# DETECTOR01.net
KiCad netlist of a schematic drawn in EAGLE
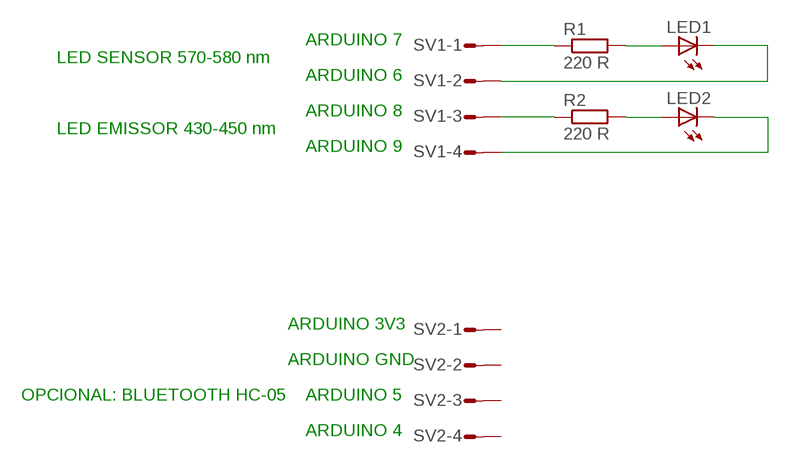
[diagram p0: schematic, sheet 1]

(export (version "E")
  (design (tool "Eeschema 10.0.6"))
  (components
    (comp (ref "LED1")
      (value "LED5MM")
      (footprint "eagle-import:LED5MM")
      (libsource (lib "eagle-import") (part "LED5MM"))
    )
    (comp (ref "LED2")
      (value "LED5MM")
      (footprint "eagle-import:LED5MM")
      (libsource (lib "eagle-import") (part "LED5MM"))
    )
    (comp (ref "R1")
      (value "220 R")
      (footprint "eagle-import:0204_7")
      (libsource (lib "eagle-import") (part "R-EU_0204/7"))
    )
    (comp (ref "R2")
      (value "220 R")
      (footprint "eagle-import:0204_7")
      (libsource (lib "eagle-import") (part "R-EU_0204/7"))
    )
    (comp (ref "SV1")
      (value "L04P")
      (footprint "eagle-import:L04P")
      (libsource (lib "eagle-import") (part "L04P"))
    )
    (comp (ref "SV2")
      (value "L04P")
      (footprint "eagle-import:L04P")
      (libsource (lib "eagle-import") (part "L04P"))
    )
  )
  (nets
    (net (code "1") (name "Net-(LED1-C)") (class "Default")
      (node (ref "LED1") (pin "K") (pinfunction "C_K") (pintype "passive"))
      (node (ref "SV1") (pin "2") (pinfunction "S_2") (pintype "passive"))
    )
    (net (code "2") (name "Net-(LED1-PadA)") (class "Default")
      (node (ref "LED1") (pin "A") (pinfunction "A_A") (pintype "passive"))
      (node (ref "R1") (pin "2") (pinfunction "2_2") (pintype "passive"))
    )
    (net (code "3") (name "Net-(LED2-C)") (class "Default")
      (node (ref "LED2") (pin "K") (pinfunction "C_K") (pintype "passive"))
      (node (ref "SV1") (pin "4") (pinfunction "S_4") (pintype "passive"))
    )
    (net (code "4") (name "Net-(LED2-PadA)") (class "Default")
      (node (ref "LED2") (pin "A") (pinfunction "A_A") (pintype "passive"))
      (node (ref "R2") (pin "2") (pinfunction "2_2") (pintype "passive"))
    )
    (net (code "5") (name "Net-(SV1A-S)") (class "Default")
      (node (ref "R1") (pin "1") (pinfunction "1_1") (pintype "passive"))
      (node (ref "SV1") (pin "1") (pinfunction "S_1") (pintype "passive"))
    )
    (net (code "6") (name "Net-(SV1C-S)") (class "Default")
      (node (ref "R2") (pin "1") (pinfunction "1_1") (pintype "passive"))
      (node (ref "SV1") (pin "3") (pinfunction "S_3") (pintype "passive"))
    )
    (net (code "7") (name "unconnected-(SV2A-S-Pad1)") (class "Default")
      (node (ref "SV2") (pin "1") (pinfunction "S_1") (pintype "passive"))
    )
    (net (code "8") (name "unconnected-(SV2B-S-Pad2)") (class "Default")
      (node (ref "SV2") (pin "2") (pinfunction "S_2") (pintype "passive"))
    )
    (net (code "9") (name "unconnected-(SV2C-S-Pad3)") (class "Default")
      (node (ref "SV2") (pin "3") (pinfunction "S_3") (pintype "passive"))
    )
    (net (code "10") (name "unconnected-(SV2D-S-Pad4)") (class "Default")
      (node (ref "SV2") (pin "4") (pinfunction "S_4") (pintype "passive"))
    )
  )
)
